# ADC.net
KiCad netlist of a schematic drawn in Altium Designer
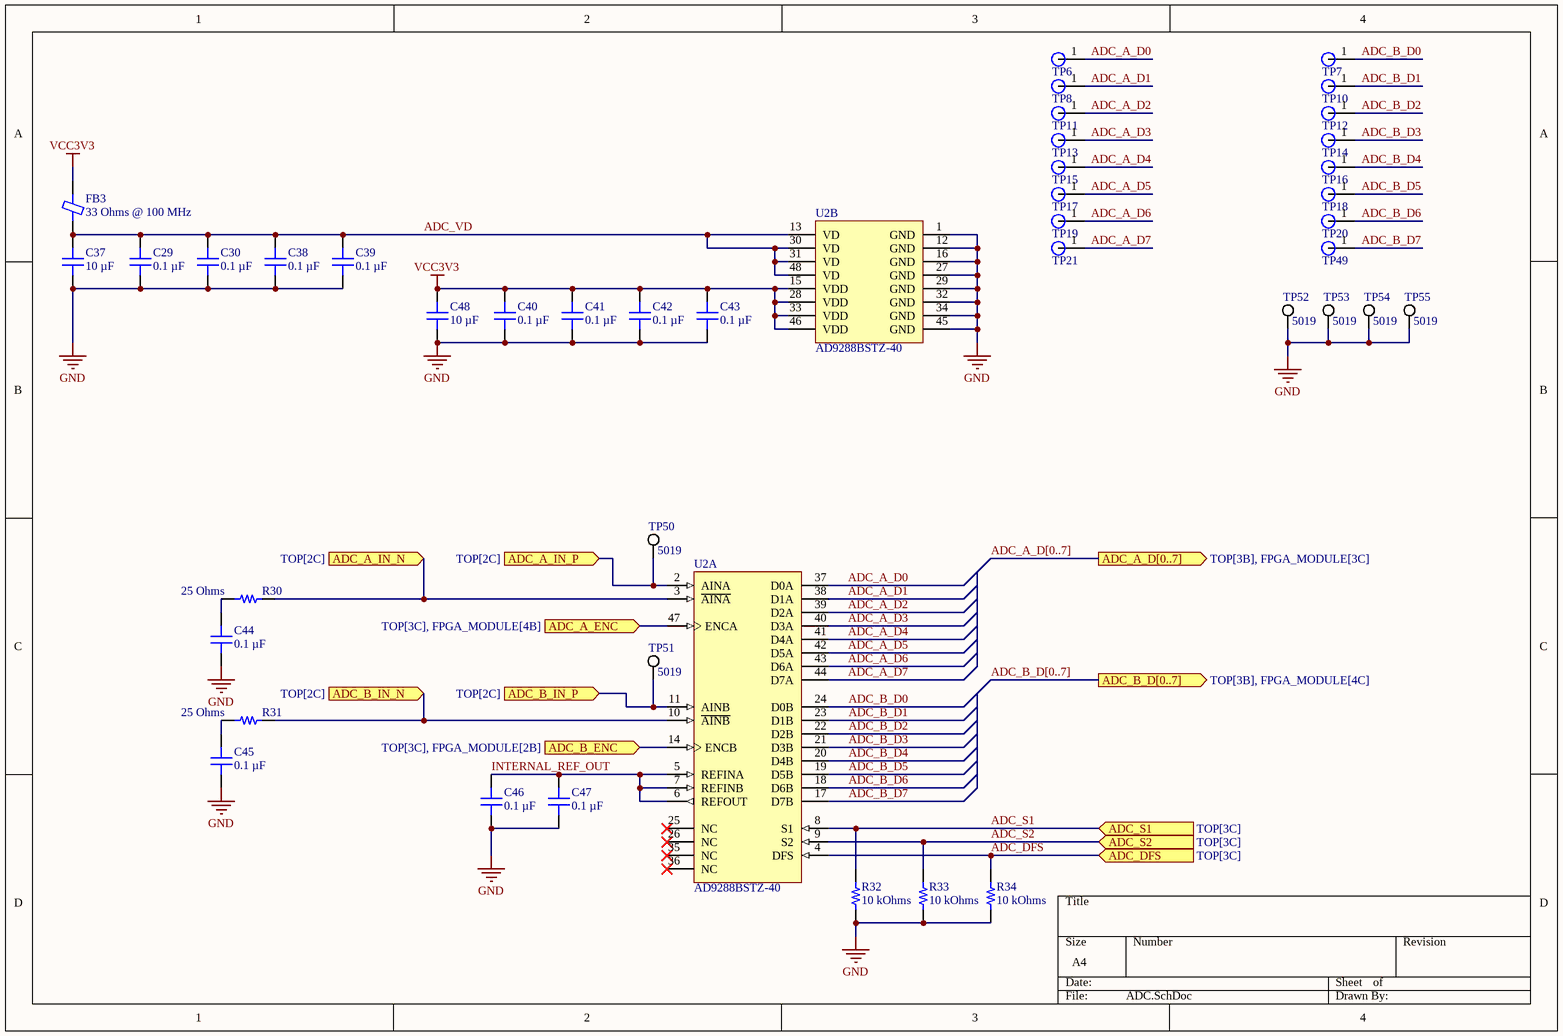
[diagram p0: ADC.SchDoc]

(export (version "E")
  (design (tool "Eeschema 10.0.6"))
  (components
    (comp (ref "C29")
      (value "0.1 µF")
      (footprint "CAP 0402_1005")
      (description "CAP CER 0.1UF 50V X5R 0402")
      (fields
        (field (name "PART NUMBER") "CGA2B3X5R1H104M050BB")
        (field (name "MANUFACTURER") "TDK Corporation")
      )
      (libsource (lib "Celestial") (part "Capacitor"))
    )
    (comp (ref "C30")
      (value "0.1 µF")
      (footprint "CAP 0402_1005")
      (description "CAP CER 0.1UF 50V X5R 0402")
      (fields
        (field (name "PART NUMBER") "CGA2B3X5R1H104M050BB")
        (field (name "MANUFACTURER") "TDK Corporation")
      )
      (libsource (lib "Celestial") (part "Capacitor"))
    )
    (comp (ref "C37")
      (value "10 µF")
      (footprint "CAP 0402_1005")
      (description "CAP CER 10UF 10V X5R 0402")
      (fields
        (field (name "PART NUMBER") "CL05A106MP8NUB8")
        (field (name "MANUFACTURER") "Samsung Electro-Mechanics")
      )
      (libsource (lib "Celestial") (part "Capacitor"))
    )
    (comp (ref "C38")
      (value "0.1 µF")
      (footprint "CAP 0402_1005")
      (description "CAP CER 0.1UF 50V X5R 0402")
      (fields
        (field (name "PART NUMBER") "CGA2B3X5R1H104M050BB")
        (field (name "MANUFACTURER") "TDK Corporation")
      )
      (libsource (lib "Celestial") (part "Capacitor"))
    )
    (comp (ref "C39")
      (value "0.1 µF")
      (footprint "CAP 0402_1005")
      (description "CAP CER 0.1UF 50V X5R 0402")
      (fields
        (field (name "PART NUMBER") "CGA2B3X5R1H104M050BB")
        (field (name "MANUFACTURER") "TDK Corporation")
      )
      (libsource (lib "Celestial") (part "Capacitor"))
    )
    (comp (ref "C40")
      (value "0.1 µF")
      (footprint "CAP 0402_1005")
      (description "CAP CER 0.1UF 50V X5R 0402")
      (fields
        (field (name "PART NUMBER") "CGA2B3X5R1H104M050BB")
        (field (name "MANUFACTURER") "TDK Corporation")
      )
      (libsource (lib "Celestial") (part "Capacitor"))
    )
    (comp (ref "C41")
      (value "0.1 µF")
      (footprint "CAP 0402_1005")
      (description "CAP CER 0.1UF 50V X5R 0402")
      (fields
        (field (name "PART NUMBER") "CGA2B3X5R1H104M050BB")
        (field (name "MANUFACTURER") "TDK Corporation")
      )
      (libsource (lib "Celestial") (part "Capacitor"))
    )
    (comp (ref "C42")
      (value "0.1 µF")
      (footprint "CAP 0402_1005")
      (description "CAP CER 0.1UF 50V X5R 0402")
      (fields
        (field (name "PART NUMBER") "CGA2B3X5R1H104M050BB")
        (field (name "MANUFACTURER") "TDK Corporation")
      )
      (libsource (lib "Celestial") (part "Capacitor"))
    )
    (comp (ref "C43")
      (value "0.1 µF")
      (footprint "CAP 0402_1005")
      (description "CAP CER 0.1UF 50V X5R 0402")
      (fields
        (field (name "PART NUMBER") "CGA2B3X5R1H104M050BB")
        (field (name "MANUFACTURER") "TDK Corporation")
      )
      (libsource (lib "Celestial") (part "Capacitor"))
    )
    (comp (ref "C44")
      (value "0.1 µF")
      (footprint "CAP 0402_1005")
      (description "CAP CER 0.1UF 50V X5R 0402")
      (fields
        (field (name "PART NUMBER") "CGA2B3X5R1H104M050BB")
        (field (name "MANUFACTURER") "TDK Corporation")
      )
      (libsource (lib "Celestial") (part "Capacitor"))
    )
    (comp (ref "C45")
      (value "0.1 µF")
      (footprint "CAP 0402_1005")
      (description "CAP CER 0.1UF 50V X5R 0402")
      (fields
        (field (name "PART NUMBER") "CGA2B3X5R1H104M050BB")
        (field (name "MANUFACTURER") "TDK Corporation")
      )
      (libsource (lib "Celestial") (part "Capacitor"))
    )
    (comp (ref "C46")
      (value "0.1 µF")
      (footprint "CAP 0402_1005")
      (description "CAP CER 0.1UF 50V X5R 0402")
      (fields
        (field (name "PART NUMBER") "CGA2B3X5R1H104M050BB")
        (field (name "MANUFACTURER") "TDK Corporation")
      )
      (libsource (lib "Celestial") (part "Capacitor"))
    )
    (comp (ref "C47")
      (value "0.1 µF")
      (footprint "CAP 0402_1005")
      (description "CAP CER 0.1UF 50V X5R 0402")
      (fields
        (field (name "PART NUMBER") "CGA2B3X5R1H104M050BB")
        (field (name "MANUFACTURER") "TDK Corporation")
      )
      (libsource (lib "Celestial") (part "Capacitor"))
    )
    (comp (ref "C48")
      (value "10 µF")
      (footprint "CAP 0402_1005")
      (description "CAP CER 10UF 10V X5R 0402")
      (fields
        (field (name "PART NUMBER") "CL05A106MP8NUB8")
        (field (name "MANUFACTURER") "Samsung Electro-Mechanics")
      )
      (libsource (lib "Celestial") (part "Capacitor"))
    )
    (comp (ref "FB3")
      (value "33 Ohms @ 100 MHz")
      (footprint "FER 0201_0603")
      (description "FERRITE BEAD 33 OHM 0201 1LN")
      (fields (field (name "PART NUMBER") "MMZ0603F330CT000") (field (name "MANUFACTURER") "TDK Corporation"))
      (libsource (lib "Celestial") (part "Ferrite Chip"))
    )
    (comp (ref "R30")
      (value "25 Ohms")
      (footprint "RES 0402_1005")
      (description "RES 25 OHM 0.1% 1/20W 0402")
      (fields (field (name "PART NUMBER") "FC0402E25R0BST0") (field (name "MANUFACTURER") "Vishay Thin Film"))
      (libsource (lib "Celestial") (part "Resistor"))
    )
    (comp (ref "R31")
      (value "25 Ohms")
      (footprint "RES 0402_1005")
      (description "RES 25 OHM 0.1% 1/20W 0402")
      (fields (field (name "PART NUMBER") "FC0402E25R0BST0") (field (name "MANUFACTURER") "Vishay Thin Film"))
      (libsource (lib "Celestial") (part "Resistor"))
    )
    (comp (ref "R32")
      (value "10 kOhms")
      (footprint "RES 0402_1005")
      (description "RES 10K OHM 0.1% 1/10W 0402")
      (fields
        (field (name "PART NUMBER") "RP73PF1E10KBTD")
        (field (name "MANUFACTURER") "TE Connectivity Passive Product")
      )
      (libsource (lib "Celestial") (part "Resistor"))
    )
    (comp (ref "R33")
      (value "10 kOhms")
      (footprint "RES 0402_1005")
      (description "RES 10K OHM 0.1% 1/10W 0402")
      (fields
        (field (name "PART NUMBER") "RP73PF1E10KBTD")
        (field (name "MANUFACTURER") "TE Connectivity Passive Product")
      )
      (libsource (lib "Celestial") (part "Resistor"))
    )
    (comp (ref "R34")
      (value "10 kOhms")
      (footprint "RES 0402_1005")
      (description "RES 10K OHM 0.1% 1/10W 0402")
      (fields
        (field (name "PART NUMBER") "RP73PF1E10KBTD")
        (field (name "MANUFACTURER") "TE Connectivity Passive Product")
      )
      (libsource (lib "Celestial") (part "Resistor"))
    )
    (comp (ref "TP6") (value "Test Point") (footprint "ethan:TP1") (libsource (lib "ethan") (part "TP1")))
    (comp (ref "TP7") (value "Test Point") (footprint "ethan:TP1") (libsource (lib "ethan") (part "TP1")))
    (comp (ref "TP8") (value "Test Point") (footprint "ethan:TP1") (libsource (lib "ethan") (part "TP1")))
    (comp (ref "TP10") (value "Test Point") (footprint "ethan:TP1") (libsource (lib "ethan") (part "TP1")))
    (comp (ref "TP11") (value "Test Point") (footprint "ethan:TP1") (libsource (lib "ethan") (part "TP1")))
    (comp (ref "TP12") (value "Test Point") (footprint "ethan:TP1") (libsource (lib "ethan") (part "TP1")))
    (comp (ref "TP13") (value "Test Point") (footprint "ethan:TP1") (libsource (lib "ethan") (part "TP1")))
    (comp (ref "TP14") (value "Test Point") (footprint "ethan:TP1") (libsource (lib "ethan") (part "TP1")))
    (comp (ref "TP15") (value "Test Point") (footprint "ethan:TP1") (libsource (lib "ethan") (part "TP1")))
    (comp (ref "TP16") (value "Test Point") (footprint "ethan:TP1") (libsource (lib "ethan") (part "TP1")))
    (comp (ref "TP17") (value "Test Point") (footprint "ethan:TP1") (libsource (lib "ethan") (part "TP1")))
    (comp (ref "TP18") (value "Test Point") (footprint "ethan:TP1") (libsource (lib "ethan") (part "TP1")))
    (comp (ref "TP19") (value "Test Point") (footprint "ethan:TP1") (libsource (lib "ethan") (part "TP1")))
    (comp (ref "TP20") (value "Test Point") (footprint "ethan:TP1") (libsource (lib "ethan") (part "TP1")))
    (comp (ref "TP21") (value "Test Point") (footprint "ethan:TP1") (libsource (lib "ethan") (part "TP1")))
    (comp (ref "TP49") (value "Test Point") (footprint "ethan:TP1") (libsource (lib "ethan") (part "TP1")))
    (comp (ref "TP50")
      (value "5019")
      (footprint "KSTN-5019_V")
      (description "Test Point, 1 Position SMD, RoHS, Tape and Reel")
      (libsource (lib "Altium Content Vault") (part "TESTPOINT_WHITE"))
    )
    (comp (ref "TP51")
      (value "5019")
      (footprint "KSTN-5019_V")
      (description "Test Point, 1 Position SMD, RoHS, Tape and Reel")
      (libsource (lib "Altium Content Vault") (part "TESTPOINT_WHITE"))
    )
    (comp (ref "TP52")
      (value "5019")
      (footprint "KSTN-5019_V")
      (description "Test Point, 1 Position SMD, RoHS, Tape and Reel")
      (libsource (lib "Altium Content Vault") (part "TESTPOINT_WHITE"))
    )
    (comp (ref "TP53")
      (value "5019")
      (footprint "KSTN-5019_V")
      (description "Test Point, 1 Position SMD, RoHS, Tape and Reel")
      (libsource (lib "Altium Content Vault") (part "TESTPOINT_WHITE"))
    )
    (comp (ref "TP54")
      (value "5019")
      (footprint "KSTN-5019_V")
      (description "Test Point, 1 Position SMD, RoHS, Tape and Reel")
      (libsource (lib "Altium Content Vault") (part "TESTPOINT_WHITE"))
    )
    (comp (ref "TP55")
      (value "5019")
      (footprint "KSTN-5019_V")
      (description "Test Point, 1 Position SMD, RoHS, Tape and Reel")
      (libsource (lib "Altium Content Vault") (part "TESTPOINT_WHITE"))
    )
    (comp (ref "U2")
      (value "AD9288BSTZ-40")
      (footprint "ST-48_M")
      (fields (field (name "GENERIC PART NUMBER") "AD9288-40") (field (name "MANUFACTURER") "Analog Devices"))
      (libsource (lib "") (part "ADI-AD9288-40-ST-48_1"))
    )
  )
  (nets
    (net (code "1") (name "/ADC_A_D0") (class "Default")
      (node (ref "TP6") (pin "1") (pinfunction "1_1") (pintype "passive"))
      (node (ref "U2") (pin "37") (pinfunction "D0A_37") (pintype "tri_state"))
    )
    (net (code "2") (name "/ADC_A_D1") (class "Default")
      (node (ref "TP8") (pin "1") (pinfunction "1_1") (pintype "passive"))
      (node (ref "U2") (pin "38") (pinfunction "D1A_38") (pintype "tri_state"))
    )
    (net (code "3") (name "/ADC_A_D2") (class "Default")
      (node (ref "TP11") (pin "1") (pinfunction "1_1") (pintype "passive"))
      (node (ref "U2") (pin "39") (pinfunction "D2A_39") (pintype "tri_state"))
    )
    (net (code "4") (name "/ADC_A_D3") (class "Default")
      (node (ref "TP13") (pin "1") (pinfunction "1_1") (pintype "passive"))
      (node (ref "U2") (pin "40") (pinfunction "D3A_40") (pintype "tri_state"))
    )
    (net (code "5") (name "/ADC_A_D4") (class "Default")
      (node (ref "TP15") (pin "1") (pinfunction "1_1") (pintype "passive"))
      (node (ref "U2") (pin "41") (pinfunction "D4A_41") (pintype "tri_state"))
    )
    (net (code "6") (name "/ADC_A_D5") (class "Default")
      (node (ref "TP17") (pin "1") (pinfunction "1_1") (pintype "passive"))
      (node (ref "U2") (pin "42") (pinfunction "D5A_42") (pintype "tri_state"))
    )
    (net (code "7") (name "/ADC_A_D6") (class "Default")
      (node (ref "TP19") (pin "1") (pinfunction "1_1") (pintype "passive"))
      (node (ref "U2") (pin "43") (pinfunction "D6A_43") (pintype "tri_state"))
    )
    (net (code "8") (name "/ADC_A_D7") (class "Default")
      (node (ref "TP21") (pin "1") (pinfunction "1_1") (pintype "passive"))
      (node (ref "U2") (pin "44") (pinfunction "D7A_44") (pintype "tri_state"))
    )
    (net (code "10") (name "/ADC_A_ENC") (class "Default")
      (node (ref "U2") (pin "47") (pinfunction "ENCA_47") (pintype "input"))
    )
    (net (code "11") (name "/ADC_A_IN_N") (class "Default")
      (node (ref "R30") (pin "2") (pinfunction "2_2") (pintype "passive"))
      (node (ref "U2") (pin "3") (pinfunction "~{AINA}_3") (pintype "input"))
    )
    (net (code "12") (name "/ADC_A_IN_P") (class "Default")
      (node (ref "TP50") (pin "1") (pinfunction "1_1") (pintype "passive"))
      (node (ref "U2") (pin "2") (pinfunction "AINA_2") (pintype "input"))
    )
    (net (code "13") (name "/ADC_B_D0") (class "Default")
      (node (ref "TP7") (pin "1") (pinfunction "1_1") (pintype "passive"))
      (node (ref "U2") (pin "24") (pinfunction "D0B_24") (pintype "tri_state"))
    )
    (net (code "14") (name "/ADC_B_D1") (class "Default")
      (node (ref "TP10") (pin "1") (pinfunction "1_1") (pintype "passive"))
      (node (ref "U2") (pin "23") (pinfunction "D1B_23") (pintype "tri_state"))
    )
    (net (code "15") (name "/ADC_B_D2") (class "Default")
      (node (ref "TP12") (pin "1") (pinfunction "1_1") (pintype "passive"))
      (node (ref "U2") (pin "22") (pinfunction "D2B_22") (pintype "tri_state"))
    )
    (net (code "16") (name "/ADC_B_D3") (class "Default")
      (node (ref "TP14") (pin "1") (pinfunction "1_1") (pintype "passive"))
      (node (ref "U2") (pin "21") (pinfunction "D3B_21") (pintype "tri_state"))
    )
    (net (code "17") (name "/ADC_B_D4") (class "Default")
      (node (ref "TP16") (pin "1") (pinfunction "1_1") (pintype "passive"))
      (node (ref "U2") (pin "20") (pinfunction "D4B_20") (pintype "tri_state"))
    )
    (net (code "18") (name "/ADC_B_D5") (class "Default")
      (node (ref "TP18") (pin "1") (pinfunction "1_1") (pintype "passive"))
      (node (ref "U2") (pin "19") (pinfunction "D5B_19") (pintype "tri_state"))
    )
    (net (code "19") (name "/ADC_B_D6") (class "Default")
      (node (ref "TP20") (pin "1") (pinfunction "1_1") (pintype "passive"))
      (node (ref "U2") (pin "18") (pinfunction "D6B_18") (pintype "tri_state"))
    )
    (net (code "20") (name "/ADC_B_D7") (class "Default")
      (node (ref "TP49") (pin "1") (pinfunction "1_1") (pintype "passive"))
      (node (ref "U2") (pin "17") (pinfunction "D7B_17") (pintype "tri_state"))
    )
    (net (code "22") (name "/ADC_B_ENC") (class "Default")
      (node (ref "U2") (pin "14") (pinfunction "ENCB_14") (pintype "input"))
    )
    (net (code "23") (name "/ADC_B_IN_N") (class "Default")
      (node (ref "R31") (pin "2") (pinfunction "2_2") (pintype "passive"))
      (node (ref "U2") (pin "10") (pinfunction "~{AINB}_10") (pintype "input"))
    )
    (net (code "24") (name "/ADC_B_IN_P") (class "Default")
      (node (ref "TP51") (pin "1") (pinfunction "1_1") (pintype "passive"))
      (node (ref "U2") (pin "11") (pinfunction "AINB_11") (pintype "input"))
    )
    (net (code "25") (name "/ADC_DFS") (class "Default")
      (node (ref "R34") (pin "2") (pinfunction "2_2") (pintype "passive"))
      (node (ref "U2") (pin "4") (pinfunction "DFS_4") (pintype "input"))
    )
    (net (code "26") (name "/ADC_S1") (class "Default")
      (node (ref "R32") (pin "2") (pinfunction "2_2") (pintype "passive"))
      (node (ref "U2") (pin "8") (pinfunction "S1_8") (pintype "input"))
    )
    (net (code "27") (name "/ADC_S2") (class "Default")
      (node (ref "R33") (pin "2") (pinfunction "2_2") (pintype "passive"))
      (node (ref "U2") (pin "9") (pinfunction "S2_9") (pintype "input"))
    )
    (net (code "28") (name "/ADC_VD") (class "Default")
      (node (ref "C29") (pin "2") (pinfunction "2_2") (pintype "passive"))
      (node (ref "C30") (pin "2") (pinfunction "2_2") (pintype "passive"))
      (node (ref "C37") (pin "2") (pinfunction "2_2") (pintype "passive"))
      (node (ref "C38") (pin "2") (pinfunction "2_2") (pintype "passive"))
      (node (ref "C39") (pin "2") (pinfunction "2_2") (pintype "passive"))
      (node (ref "FB3") (pin "2") (pinfunction "2_2") (pintype "passive"))
      (node (ref "U2") (pin "13") (pinfunction "VD_13") (pintype "power_in"))
      (node (ref "U2") (pin "30") (pinfunction "VD_30") (pintype "power_in"))
      (node (ref "U2") (pin "31") (pinfunction "VD_31") (pintype "power_in"))
      (node (ref "U2") (pin "48") (pinfunction "VD_48") (pintype "power_in"))
    )
    (net (code "29") (name "/INTERNAL_REF_OUT") (class "Default")
      (node (ref "C46") (pin "2") (pinfunction "2_2") (pintype "passive"))
      (node (ref "C47") (pin "2") (pinfunction "2_2") (pintype "passive"))
      (node (ref "U2") (pin "5") (pinfunction "REFINA_5") (pintype "input"))
      (node (ref "U2") (pin "6") (pinfunction "REFOUT_6") (pintype "output"))
      (node (ref "U2") (pin "7") (pinfunction "REFINB_7") (pintype "input"))
    )
    (net (code "30") (name "GND") (class "Default")
      (node (ref "C29") (pin "1") (pinfunction "1_1") (pintype "passive"))
      (node (ref "C30") (pin "1") (pinfunction "1_1") (pintype "passive"))
      (node (ref "C37") (pin "1") (pinfunction "1_1") (pintype "passive"))
      (node (ref "C38") (pin "1") (pinfunction "1_1") (pintype "passive"))
      (node (ref "C39") (pin "1") (pinfunction "1_1") (pintype "passive"))
      (node (ref "C40") (pin "1") (pinfunction "1_1") (pintype "passive"))
      (node (ref "C41") (pin "1") (pinfunction "1_1") (pintype "passive"))
      (node (ref "C42") (pin "1") (pinfunction "1_1") (pintype "passive"))
      (node (ref "C43") (pin "1") (pinfunction "1_1") (pintype "passive"))
      (node (ref "C44") (pin "1") (pinfunction "1_1") (pintype "passive"))
      (node (ref "C45") (pin "1") (pinfunction "1_1") (pintype "passive"))
      (node (ref "C46") (pin "1") (pinfunction "1_1") (pintype "passive"))
      (node (ref "C47") (pin "1") (pinfunction "1_1") (pintype "passive"))
      (node (ref "C48") (pin "1") (pinfunction "1_1") (pintype "passive"))
      (node (ref "R32") (pin "1") (pinfunction "1_1") (pintype "passive"))
      (node (ref "R33") (pin "1") (pinfunction "1_1") (pintype "passive"))
      (node (ref "R34") (pin "1") (pinfunction "1_1") (pintype "passive"))
      (node (ref "TP52") (pin "1") (pinfunction "1_1") (pintype "passive"))
      (node (ref "TP53") (pin "1") (pinfunction "1_1") (pintype "passive"))
      (node (ref "TP54") (pin "1") (pinfunction "1_1") (pintype "passive"))
      (node (ref "TP55") (pin "1") (pinfunction "1_1") (pintype "passive"))
      (node (ref "U2") (pin "1") (pinfunction "GND_1") (pintype "power_in"))
      (node (ref "U2") (pin "12") (pinfunction "GND_12") (pintype "power_in"))
      (node (ref "U2") (pin "16") (pinfunction "GND_16") (pintype "power_in"))
      (node (ref "U2") (pin "27") (pinfunction "GND_27") (pintype "power_in"))
      (node (ref "U2") (pin "29") (pinfunction "GND_29") (pintype "power_in"))
      (node (ref "U2") (pin "32") (pinfunction "GND_32") (pintype "power_in"))
      (node (ref "U2") (pin "34") (pinfunction "GND_34") (pintype "power_in"))
      (node (ref "U2") (pin "45") (pinfunction "GND_45") (pintype "power_in"))
    )
    (net (code "31") (name "Net-(C44-Pad2)") (class "Default")
      (node (ref "C44") (pin "2") (pinfunction "2_2") (pintype "passive"))
      (node (ref "R30") (pin "1") (pinfunction "1_1") (pintype "passive"))
    )
    (net (code "32") (name "Net-(C45-Pad2)") (class "Default")
      (node (ref "C45") (pin "2") (pinfunction "2_2") (pintype "passive"))
      (node (ref "R31") (pin "1") (pinfunction "1_1") (pintype "passive"))
    )
    (net (code "33") (name "VCC3V3") (class "Default")
      (node (ref "C40") (pin "2") (pinfunction "2_2") (pintype "passive"))
      (node (ref "C41") (pin "2") (pinfunction "2_2") (pintype "passive"))
      (node (ref "C42") (pin "2") (pinfunction "2_2") (pintype "passive"))
      (node (ref "C43") (pin "2") (pinfunction "2_2") (pintype "passive"))
      (node (ref "C48") (pin "2") (pinfunction "2_2") (pintype "passive"))
      (node (ref "FB3") (pin "1") (pinfunction "1_1") (pintype "passive"))
      (node (ref "U2") (pin "15") (pinfunction "VDD_15") (pintype "power_in"))
      (node (ref "U2") (pin "28") (pinfunction "VDD_28") (pintype "power_in"))
      (node (ref "U2") (pin "33") (pinfunction "VDD_33") (pintype "power_in"))
      (node (ref "U2") (pin "46") (pinfunction "VDD_46") (pintype "power_in"))
    )
    (net (code "34") (name "unconnected-(U2A-NC-Pad25)") (class "Default")
      (node (ref "U2") (pin "25") (pinfunction "NC_25") (pintype "passive+no_connect"))
    )
    (net (code "35") (name "unconnected-(U2A-NC-Pad26)") (class "Default")
      (node (ref "U2") (pin "26") (pinfunction "NC_26") (pintype "passive+no_connect"))
    )
    (net (code "36") (name "unconnected-(U2A-NC-Pad35)") (class "Default")
      (node (ref "U2") (pin "35") (pinfunction "NC_35") (pintype "passive+no_connect"))
    )
    (net (code "37") (name "unconnected-(U2A-NC-Pad36)") (class "Default")
      (node (ref "U2") (pin "36") (pinfunction "NC_36") (pintype "passive+no_connect"))
    )
  )
)
